# bmsMaster_can.net
KiCad netlist of a schematic drawn in Altium Designer
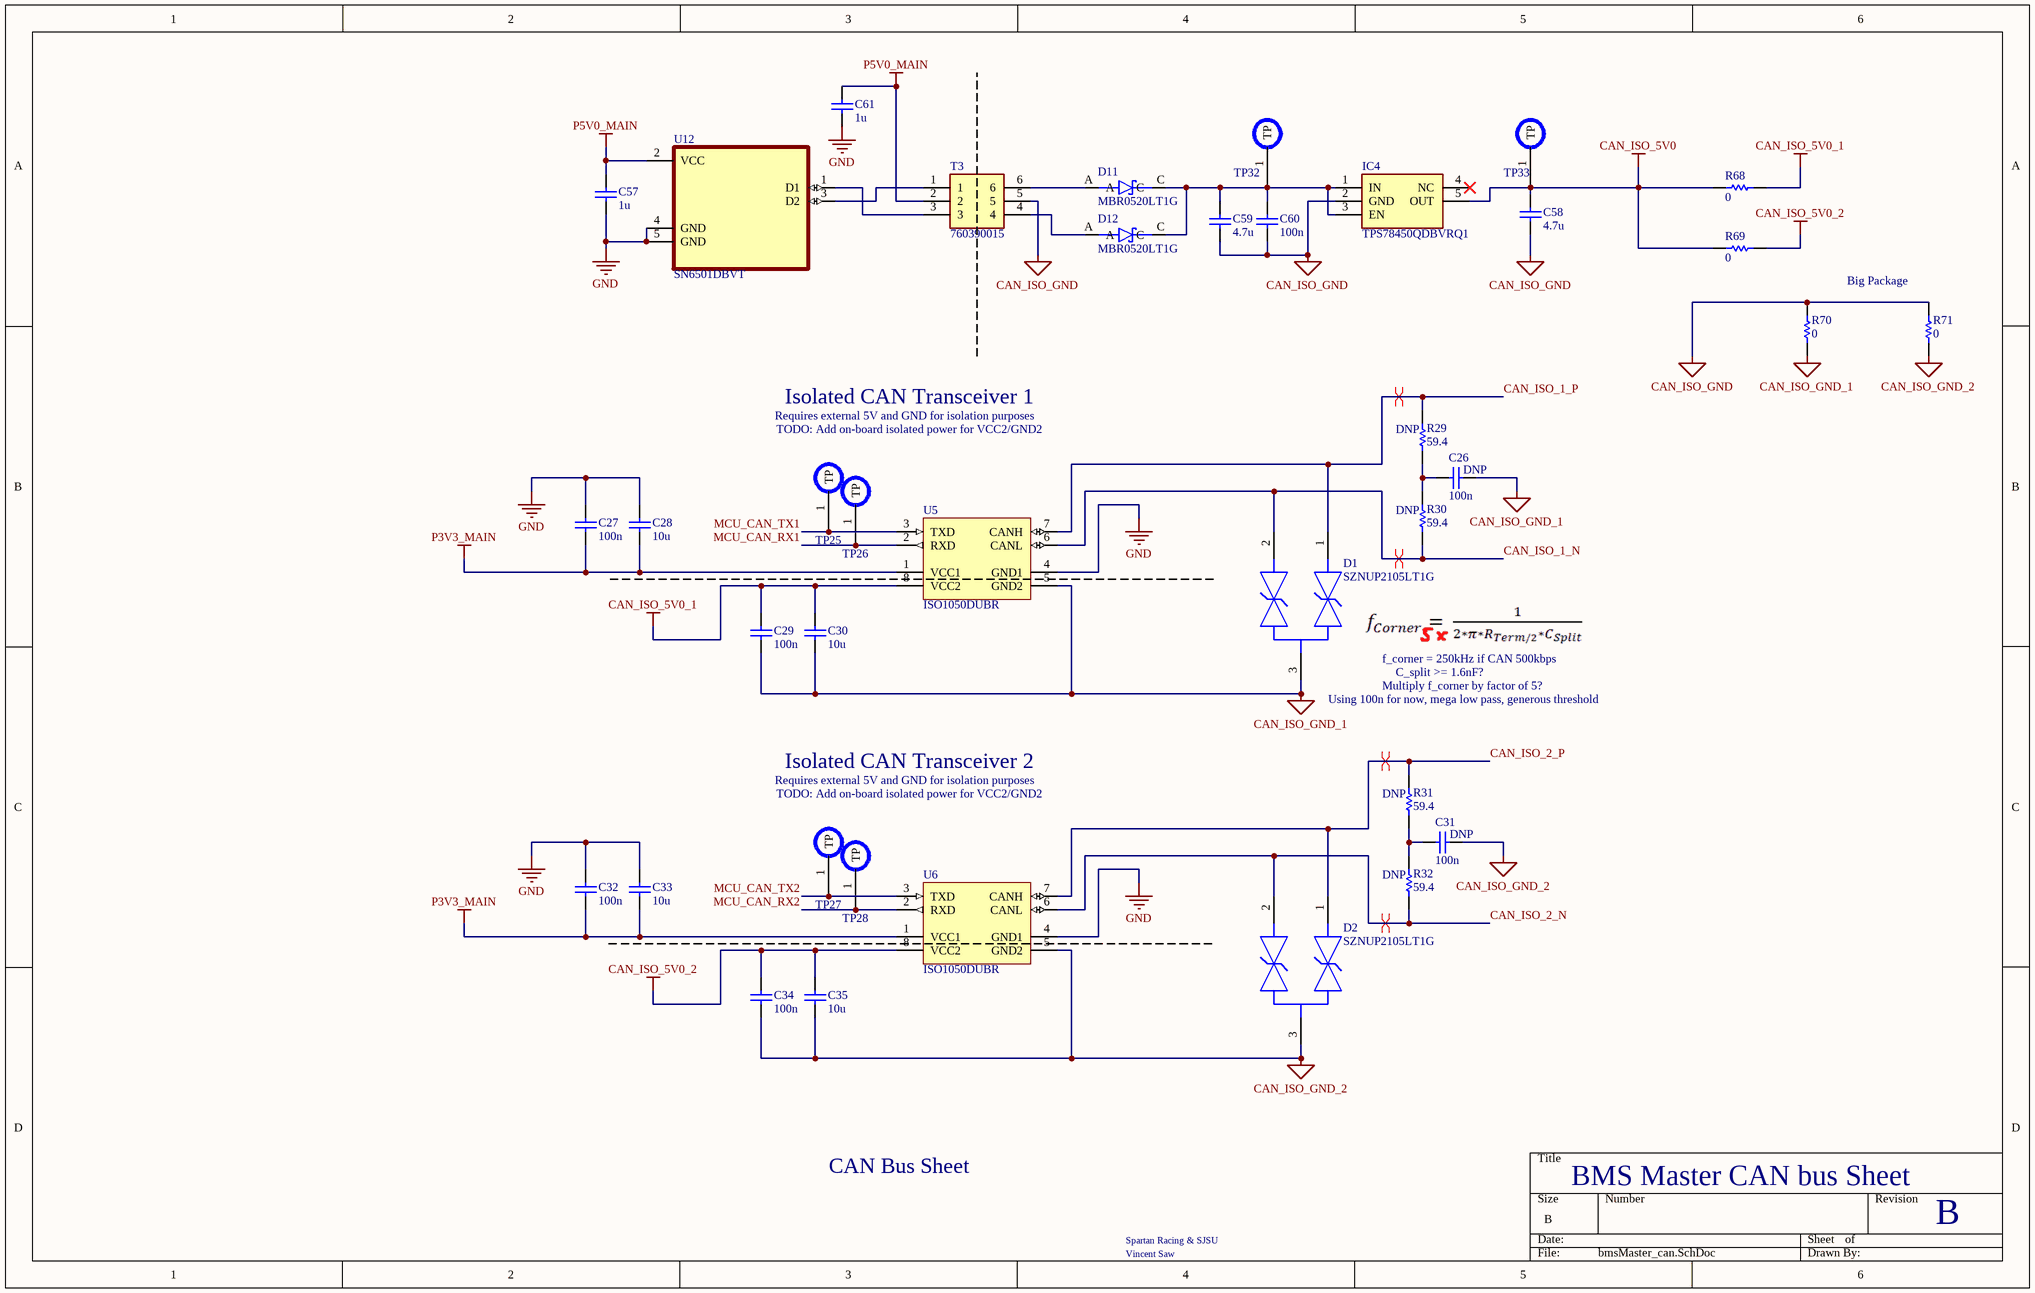
[diagram p0: bmsMaster_can.SchDoc]

(export (version "E")
  (design (tool "Eeschema 10.0.6"))
  (components
    (comp (ref "C26")
      (value "100n")
      (footprint "CAPC1608X90N")
      (description "Capacitor")
      (libsource (lib "Simulation Generic Components") (part "Capacitor"))
    )
    (comp (ref "C27")
      (value "100n")
      (footprint "CAPC1608X90N")
      (description "Capacitor")
      (libsource (lib "Simulation Generic Components") (part "Capacitor"))
    )
    (comp (ref "C28")
      (value "10u")
      (footprint "CAPC1608X90N")
      (description "Capacitor")
      (libsource (lib "Simulation Generic Components") (part "Capacitor"))
    )
    (comp (ref "C29")
      (value "100n")
      (footprint "CAPC1608X90N")
      (description "Capacitor")
      (libsource (lib "Simulation Generic Components") (part "Capacitor"))
    )
    (comp (ref "C30")
      (value "10u")
      (footprint "CAPC1608X90N")
      (description "Capacitor")
      (libsource (lib "Simulation Generic Components") (part "Capacitor"))
    )
    (comp (ref "C31")
      (value "100n")
      (footprint "CAPC1608X90N")
      (description "Capacitor")
      (libsource (lib "Simulation Generic Components") (part "Capacitor"))
    )
    (comp (ref "C32")
      (value "100n")
      (footprint "CAPC1608X90N")
      (description "Capacitor")
      (libsource (lib "Simulation Generic Components") (part "Capacitor"))
    )
    (comp (ref "C33")
      (value "10u")
      (footprint "CAPC1608X90N")
      (description "Capacitor")
      (libsource (lib "Simulation Generic Components") (part "Capacitor"))
    )
    (comp (ref "C34")
      (value "100n")
      (footprint "CAPC1608X90N")
      (description "Capacitor")
      (libsource (lib "Simulation Generic Components") (part "Capacitor"))
    )
    (comp (ref "C35")
      (value "10u")
      (footprint "CAPC1608X90N")
      (description "Capacitor")
      (libsource (lib "Simulation Generic Components") (part "Capacitor"))
    )
    (comp (ref "C57")
      (value "1u")
      (footprint "CAPC1608X90N")
      (description "Capacitor")
      (libsource (lib "Simulation Generic Components") (part "Capacitor"))
    )
    (comp (ref "C58")
      (value "4.7u")
      (footprint "CAPC1608X90N")
      (description "Capacitor")
      (libsource (lib "Simulation Generic Components") (part "Capacitor"))
    )
    (comp (ref "C59")
      (value "4.7u")
      (footprint "CAPC1608X90N")
      (description "Capacitor")
      (libsource (lib "Simulation Generic Components") (part "Capacitor"))
    )
    (comp (ref "C60")
      (value "100n")
      (footprint "CAPC1608X90N")
      (description "Capacitor")
      (libsource (lib "Simulation Generic Components") (part "Capacitor"))
    )
    (comp (ref "C61")
      (value "1u")
      (footprint "CAPC1608X90N")
      (description "Capacitor")
      (libsource (lib "Simulation Generic Components") (part "Capacitor"))
    )
    (comp (ref "D1")
      (value "SZNUP2105LT1G")
      (footprint "FP-318-08-MFG")
      (description "TVS DIODE 24V 44V SOT23-3")
      (fields
        (field (name "OCTOPART") "https://octopart.com/sznup2105lt1g-on+semiconductor-22134626")
        (field (name "MANUFACTURER") "ON Semiconductor")
      )
      (libsource (lib "Altium Content Vault") (part "9fadcfe560bc2ec8fec8016e4fb2740"))
    )
    (comp (ref "D2")
      (value "SZNUP2105LT1G")
      (footprint "FP-318-08-MFG")
      (description "TVS DIODE 24V 44V SOT23-3")
      (fields
        (field (name "OCTOPART") "https://octopart.com/sznup2105lt1g-on+semiconductor-22134626")
        (field (name "MANUFACTURER") "ON Semiconductor")
      )
      (libsource (lib "Altium Content Vault") (part "9fadcfe560bc2ec8fec8016e4fb2740"))
    )
    (comp (ref "D11")
      (value "MBR0520LT1G")
      (footprint "MBR0520LT1G:SOD3716X135N")
      (description "Rectifier, Schottky Power; Plastic Sod-123; 0.5 a @ +90c If; +125; 20v; 1000")
      (fields (field (name "MF") "{'manufacturer': u'ON Semiconductor'}"))
      (libsource (lib "*") (part "MBR0520LT1G"))
    )
    (comp (ref "D12")
      (value "MBR0520LT1G")
      (footprint "MBR0520LT1G:SOD3716X135N")
      (description "Rectifier, Schottky Power; Plastic Sod-123; 0.5 a @ +90c If; +125; 20v; 1000")
      (fields (field (name "MF") "{'manufacturer': u'ON Semiconductor'}"))
      (libsource (lib "*") (part "MBR0520LT1G"))
    )
    (comp (ref "IC4")
      (value "TPS78450QDBVRQ1")
      (footprint "SamacSys:SOT95P280X145-5N")
      (description "Integrated Circuit")
      (fields (field (name "MOUSER PART NUMBER") "595-TPS78450QDBVRQ1"))
      (libsource (lib "*") (part "TPS78450QDBVRQ1"))
    )
    (comp (ref "R29")
      (value "59.4")
      (footprint "RESC1608X50N")
      (description "Resistor")
      (libsource (lib "Simulation Generic Components") (part "Resistor"))
    )
    (comp (ref "R30")
      (value "59.4")
      (footprint "RESC1608X50N")
      (description "Resistor")
      (libsource (lib "Simulation Generic Components") (part "Resistor"))
    )
    (comp (ref "R31")
      (value "59.4")
      (footprint "RESC1608X50N")
      (description "Resistor")
      (libsource (lib "Simulation Generic Components") (part "Resistor"))
    )
    (comp (ref "R32")
      (value "59.4")
      (footprint "RESC1608X50N")
      (description "Resistor")
      (libsource (lib "Simulation Generic Components") (part "Resistor"))
    )
    (comp (ref "R68")
      (value "0")
      (footprint "RESC1608X50N")
      (description "Resistor")
      (libsource (lib "Simulation Generic Components") (part "Resistor"))
    )
    (comp (ref "R69")
      (value "0")
      (footprint "RESC1608X50N")
      (description "Resistor")
      (libsource (lib "Simulation Generic Components") (part "Resistor"))
    )
    (comp (ref "R70")
      (value "0")
      (footprint "RESC1608X50N")
      (description "Resistor")
      (libsource (lib "Simulation Generic Components") (part "Resistor"))
    )
    (comp (ref "R71")
      (value "0")
      (footprint "RESC1608X50N")
      (description "Resistor")
      (libsource (lib "Simulation Generic Components") (part "Resistor"))
    )
    (comp (ref "T3")
      (value "760390015")
      (footprint "SamacSys:760390015")
      (description "Transformer")
      (fields (field (name "MOUSER PART NUMBER") "710-760390015"))
      (libsource (lib "*") (part "760390015"))
    )
    (comp (ref "TP25")
      (value "TSTPT")
      (footprint "Testpoint1")
      (libsource (lib "testpoint1") (part "Testpoint1"))
    )
    (comp (ref "TP26")
      (value "TSTPT")
      (footprint "Testpoint1")
      (libsource (lib "testpoint1") (part "Testpoint1"))
    )
    (comp (ref "TP27")
      (value "TSTPT")
      (footprint "Testpoint1")
      (libsource (lib "testpoint1") (part "Testpoint1"))
    )
    (comp (ref "TP28")
      (value "TSTPT")
      (footprint "Testpoint1")
      (libsource (lib "testpoint1") (part "Testpoint1"))
    )
    (comp (ref "TP32")
      (value "TSTPT")
      (footprint "Testpoint1")
      (libsource (lib "testpoint1") (part "Testpoint1"))
    )
    (comp (ref "TP33")
      (value "TSTPT")
      (footprint "Testpoint1")
      (libsource (lib "testpoint1") (part "Testpoint1"))
    )
    (comp (ref "U5")
      (value "ISO1050DUBR")
      (footprint "DUB0008A_L")
      (description "Isolated CAN Transceiver, -55 to 105 degC, 8-pin SOP (DUB), Green (RoHS & no Sb/Br)")
      (fields (field (name "MANUFACTURER") "Texas Instruments"))
      (libsource (lib "Altium Content Vault") (part "TI-ISO1050-SOP_DUB-8"))
    )
    (comp (ref "U6")
      (value "ISO1050DUBR")
      (footprint "DUB0008A_L")
      (description "Isolated CAN Transceiver, -55 to 105 degC, 8-pin SOP (DUB), Green (RoHS & no Sb/Br)")
      (fields (field (name "MANUFACTURER") "Texas Instruments"))
      (libsource (lib "Altium Content Vault") (part "TI-ISO1050-SOP_DUB-8"))
    )
    (comp (ref "U12")
      (value "SN6501DBVT")
      (footprint "SN6501DBVT:SOT95P280X145-5N")
      (fields (field (name "MF") "{'manufacturer': u'Texas Instruments'}"))
      (libsource (lib "*") (part "SN6501DBVT"))
    )
  )
  (nets
    (net (code "1") (name "/CAN_ISO_1_N") (class "Default")
      (node (ref "D1") (pin "2") (pinfunction "2_2") (pintype "passive"))
      (node (ref "R30") (pin "1") (pinfunction "1_1") (pintype "passive"))
      (node (ref "U5") (pin "6") (pinfunction "CANL_6") (pintype "bidirectional"))
    )
    (net (code "2") (name "/CAN_ISO_1_P") (class "Default")
      (node (ref "D1") (pin "1") (pinfunction "1_1") (pintype "passive"))
      (node (ref "R29") (pin "2") (pinfunction "2_2") (pintype "passive"))
      (node (ref "U5") (pin "7") (pinfunction "CANH_7") (pintype "bidirectional"))
    )
    (net (code "3") (name "/CAN_ISO_2_N") (class "Default")
      (node (ref "D2") (pin "2") (pinfunction "2_2") (pintype "passive"))
      (node (ref "R32") (pin "1") (pinfunction "1_1") (pintype "passive"))
      (node (ref "U6") (pin "6") (pinfunction "CANL_6") (pintype "bidirectional"))
    )
    (net (code "4") (name "/CAN_ISO_2_P") (class "Default")
      (node (ref "D2") (pin "1") (pinfunction "1_1") (pintype "passive"))
      (node (ref "R31") (pin "2") (pinfunction "2_2") (pintype "passive"))
      (node (ref "U6") (pin "7") (pinfunction "CANH_7") (pintype "bidirectional"))
    )
    (net (code "5") (name "/MCU_CAN_RX1") (class "Default")
      (node (ref "TP26") (pin "1") (pinfunction "TP_1") (pintype "passive"))
      (node (ref "U5") (pin "2") (pinfunction "RXD_2") (pintype "output"))
    )
    (net (code "6") (name "/MCU_CAN_RX2") (class "Default")
      (node (ref "TP28") (pin "1") (pinfunction "TP_1") (pintype "passive"))
      (node (ref "U6") (pin "2") (pinfunction "RXD_2") (pintype "output"))
    )
    (net (code "7") (name "/MCU_CAN_TX1") (class "Default")
      (node (ref "TP25") (pin "1") (pinfunction "TP_1") (pintype "passive"))
      (node (ref "U5") (pin "3") (pinfunction "TXD_3") (pintype "input"))
    )
    (net (code "8") (name "/MCU_CAN_TX2") (class "Default")
      (node (ref "TP27") (pin "1") (pinfunction "TP_1") (pintype "passive"))
      (node (ref "U6") (pin "3") (pinfunction "TXD_3") (pintype "input"))
    )
    (net (code "9") (name "CAN_ISO_5V0") (class "Default")
      (node (ref "C58") (pin "2") (pinfunction "2_2") (pintype "passive"))
      (node (ref "IC4") (pin "5") (pinfunction "OUT_5") (pintype "passive"))
      (node (ref "R68") (pin "1") (pinfunction "1_1") (pintype "passive"))
      (node (ref "R69") (pin "1") (pinfunction "1_1") (pintype "passive"))
      (node (ref "TP33") (pin "1") (pinfunction "TP_1") (pintype "passive"))
    )
    (net (code "10") (name "CAN_ISO_5V0_1") (class "Default")
      (node (ref "C29") (pin "2") (pinfunction "2_2") (pintype "passive"))
      (node (ref "C30") (pin "2") (pinfunction "2_2") (pintype "passive"))
      (node (ref "R68") (pin "2") (pinfunction "2_2") (pintype "passive"))
      (node (ref "U5") (pin "8") (pinfunction "VCC2_8") (pintype "power_in"))
    )
    (net (code "11") (name "CAN_ISO_5V0_2") (class "Default")
      (node (ref "C34") (pin "2") (pinfunction "2_2") (pintype "passive"))
      (node (ref "C35") (pin "2") (pinfunction "2_2") (pintype "passive"))
      (node (ref "R69") (pin "2") (pinfunction "2_2") (pintype "passive"))
      (node (ref "U6") (pin "8") (pinfunction "VCC2_8") (pintype "power_in"))
    )
    (net (code "12") (name "CAN_ISO_GND") (class "Default")
      (node (ref "C58") (pin "1") (pinfunction "1_1") (pintype "passive"))
      (node (ref "C59") (pin "1") (pinfunction "1_1") (pintype "passive"))
      (node (ref "C60") (pin "1") (pinfunction "1_1") (pintype "passive"))
      (node (ref "IC4") (pin "2") (pinfunction "GND_2") (pintype "passive"))
      (node (ref "R70") (pin "2") (pinfunction "2_2") (pintype "passive"))
      (node (ref "R71") (pin "2") (pinfunction "2_2") (pintype "passive"))
      (node (ref "T3") (pin "5") (pinfunction "5_5") (pintype "passive"))
    )
    (net (code "13") (name "CAN_ISO_GND_1") (class "Default")
      (node (ref "C26") (pin "1") (pinfunction "1_1") (pintype "passive"))
      (node (ref "C29") (pin "1") (pinfunction "1_1") (pintype "passive"))
      (node (ref "C30") (pin "1") (pinfunction "1_1") (pintype "passive"))
      (node (ref "D1") (pin "3") (pinfunction "3_3") (pintype "passive"))
      (node (ref "R70") (pin "1") (pinfunction "1_1") (pintype "passive"))
      (node (ref "U5") (pin "5") (pinfunction "GND2_5") (pintype "power_in"))
    )
    (net (code "14") (name "CAN_ISO_GND_2") (class "Default")
      (node (ref "C31") (pin "1") (pinfunction "1_1") (pintype "passive"))
      (node (ref "C34") (pin "1") (pinfunction "1_1") (pintype "passive"))
      (node (ref "C35") (pin "1") (pinfunction "1_1") (pintype "passive"))
      (node (ref "D2") (pin "3") (pinfunction "3_3") (pintype "passive"))
      (node (ref "R71") (pin "1") (pinfunction "1_1") (pintype "passive"))
      (node (ref "U6") (pin "5") (pinfunction "GND2_5") (pintype "power_in"))
    )
    (net (code "15") (name "GND") (class "Default")
      (node (ref "C27") (pin "2") (pinfunction "2_2") (pintype "passive"))
      (node (ref "C28") (pin "2") (pinfunction "2_2") (pintype "passive"))
      (node (ref "C32") (pin "2") (pinfunction "2_2") (pintype "passive"))
      (node (ref "C33") (pin "2") (pinfunction "2_2") (pintype "passive"))
      (node (ref "C57") (pin "1") (pinfunction "1_1") (pintype "passive"))
      (node (ref "C61") (pin "1") (pinfunction "1_1") (pintype "passive"))
      (node (ref "U12") (pin "4") (pinfunction "GND_4") (pintype "power_in"))
      (node (ref "U12") (pin "5") (pinfunction "GND_5") (pintype "power_in"))
      (node (ref "U5") (pin "4") (pinfunction "GND1_4") (pintype "power_in"))
      (node (ref "U6") (pin "4") (pinfunction "GND1_4") (pintype "power_in"))
    )
    (net (code "16") (name "Net-(C26-Pad2)") (class "Default")
      (node (ref "C26") (pin "2") (pinfunction "2_2") (pintype "passive"))
      (node (ref "R29") (pin "1") (pinfunction "1_1") (pintype "passive"))
      (node (ref "R30") (pin "2") (pinfunction "2_2") (pintype "passive"))
    )
    (net (code "17") (name "Net-(C31-Pad2)") (class "Default")
      (node (ref "C31") (pin "2") (pinfunction "2_2") (pintype "passive"))
      (node (ref "R31") (pin "1") (pinfunction "1_1") (pintype "passive"))
      (node (ref "R32") (pin "2") (pinfunction "2_2") (pintype "passive"))
    )
    (net (code "18") (name "Net-(D11-PadA)") (class "Default")
      (node (ref "D11") (pin "A") (pinfunction "A_A") (pintype "passive"))
      (node (ref "T3") (pin "6") (pinfunction "6_6") (pintype "passive"))
    )
    (net (code "19") (name "Net-(D12-PadA)") (class "Default")
      (node (ref "D12") (pin "A") (pinfunction "A_A") (pintype "passive"))
      (node (ref "T3") (pin "4") (pinfunction "4_4") (pintype "passive"))
    )
    (net (code "20") (name "Net-(IC4-EN)") (class "Default")
      (node (ref "C59") (pin "2") (pinfunction "2_2") (pintype "passive"))
      (node (ref "C60") (pin "2") (pinfunction "2_2") (pintype "passive"))
      (node (ref "D11") (pin "C") (pinfunction "C_C") (pintype "passive"))
      (node (ref "D12") (pin "C") (pinfunction "C_C") (pintype "passive"))
      (node (ref "IC4") (pin "1") (pinfunction "IN_1") (pintype "passive"))
      (node (ref "IC4") (pin "3") (pinfunction "EN_3") (pintype "passive"))
      (node (ref "TP32") (pin "1") (pinfunction "TP_1") (pintype "passive"))
    )
    (net (code "21") (name "Net-(U12-D1)") (class "Default")
      (node (ref "T3") (pin "3") (pinfunction "3_3") (pintype "passive"))
      (node (ref "U12") (pin "1") (pinfunction "D1_1") (pintype "bidirectional"))
    )
    (net (code "22") (name "Net-(U12-D2)") (class "Default")
      (node (ref "T3") (pin "1") (pinfunction "1_1") (pintype "passive"))
      (node (ref "U12") (pin "3") (pinfunction "D2_3") (pintype "bidirectional"))
    )
    (net (code "23") (name "P3V3_MAIN") (class "Default")
      (node (ref "C27") (pin "1") (pinfunction "1_1") (pintype "passive"))
      (node (ref "C28") (pin "1") (pinfunction "1_1") (pintype "passive"))
      (node (ref "C32") (pin "1") (pinfunction "1_1") (pintype "passive"))
      (node (ref "C33") (pin "1") (pinfunction "1_1") (pintype "passive"))
      (node (ref "U5") (pin "1") (pinfunction "VCC1_1") (pintype "power_in"))
      (node (ref "U6") (pin "1") (pinfunction "VCC1_1") (pintype "power_in"))
    )
    (net (code "24") (name "P5V0_MAIN") (class "Default")
      (node (ref "C57") (pin "2") (pinfunction "2_2") (pintype "passive"))
      (node (ref "C61") (pin "2") (pinfunction "2_2") (pintype "passive"))
      (node (ref "T3") (pin "2") (pinfunction "2_2") (pintype "passive"))
      (node (ref "U12") (pin "2") (pinfunction "VCC_2") (pintype "power_in"))
    )
    (net (code "25") (name "unconnected-(IC4-NC-Pad4)") (class "Default")
      (node (ref "IC4") (pin "4") (pinfunction "NC_4") (pintype "passive+no_connect"))
    )
  )
)
